# Resistor_Module.net
KiCad netlist of a schematic drawn in EAGLE
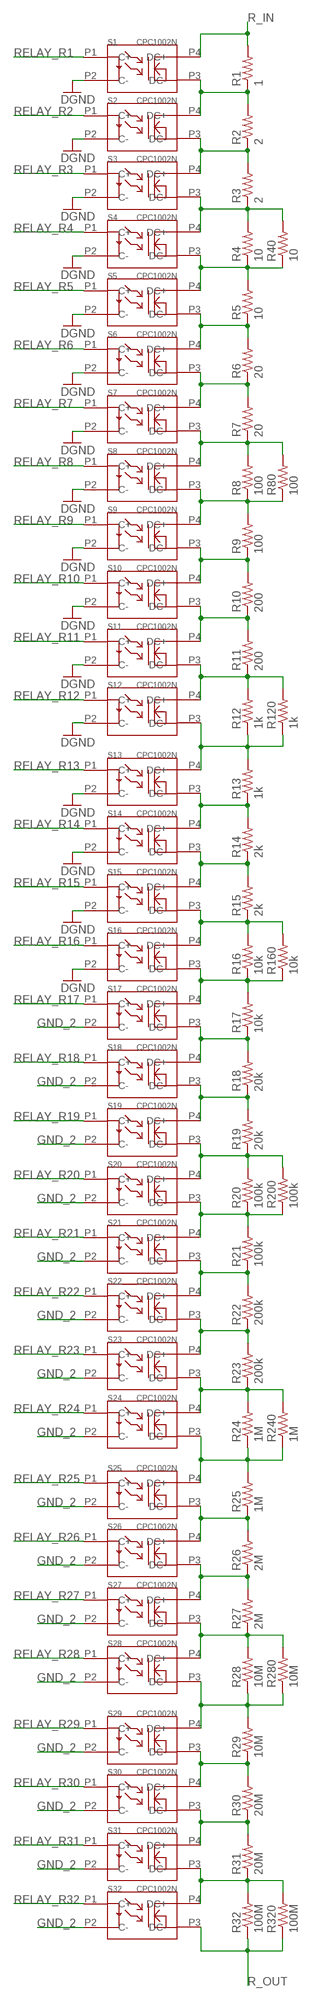
[diagram p0: schematic, sheet 1]
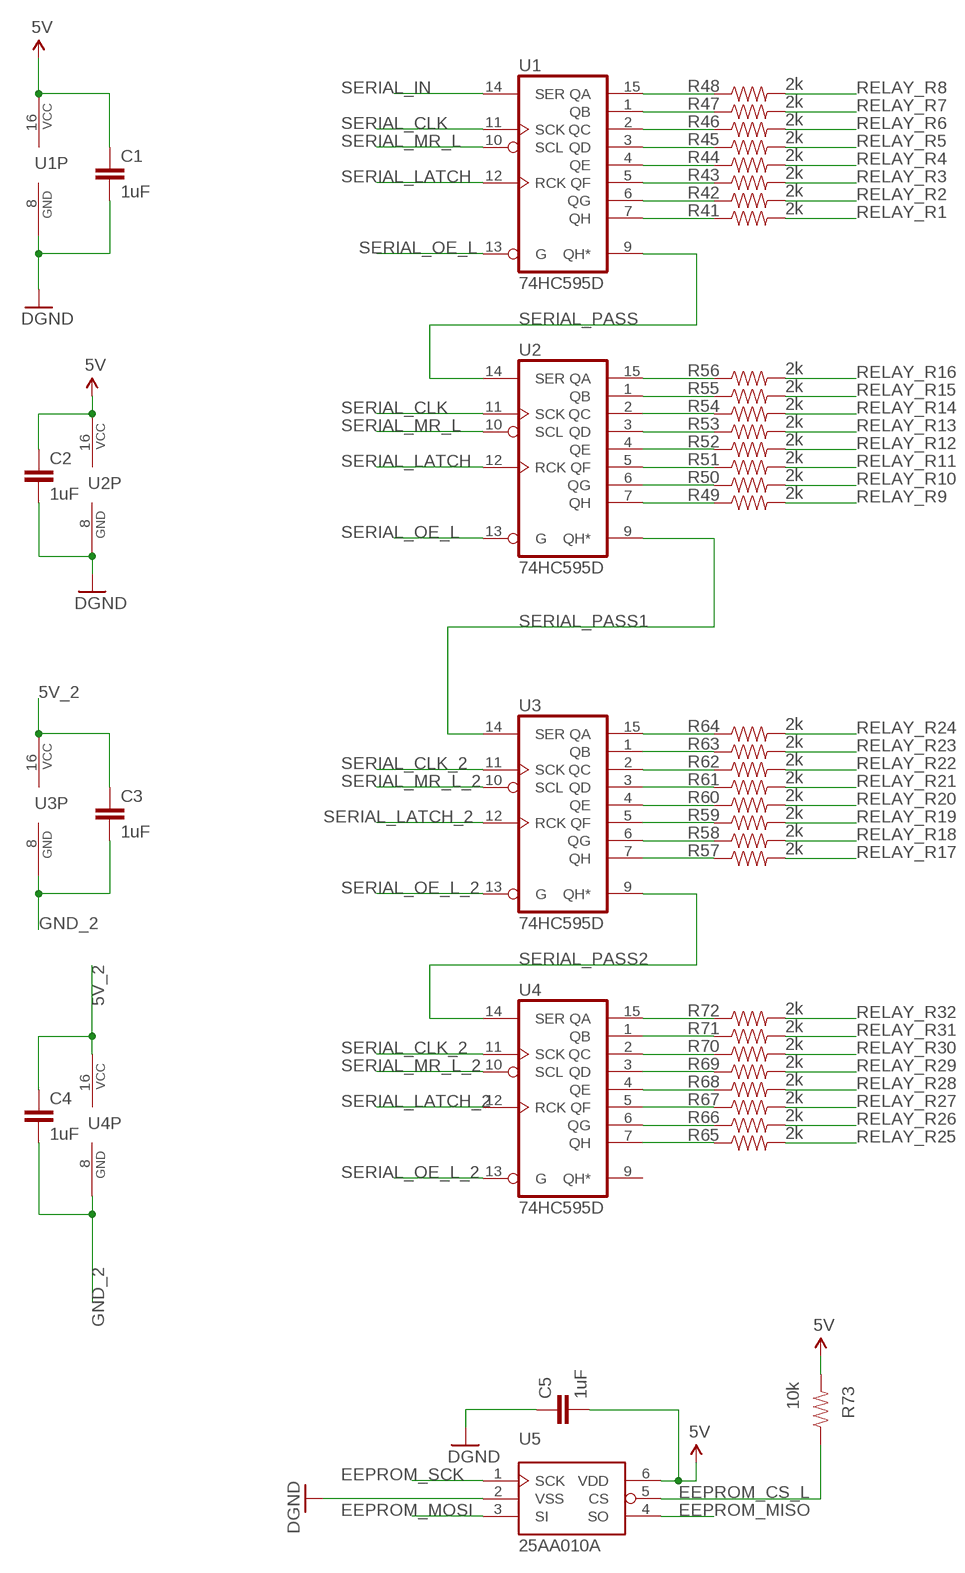
[diagram p1: schematic, sheet 2]
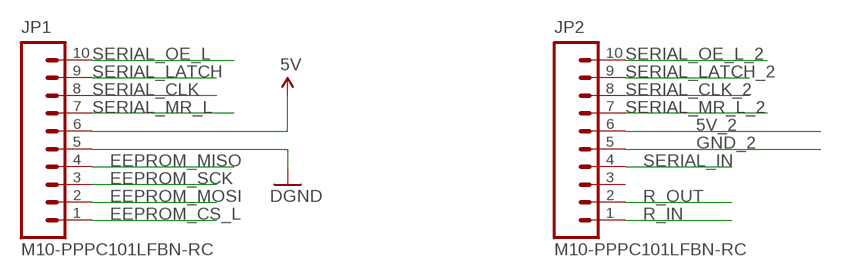
[diagram p2: schematic, sheet 3]
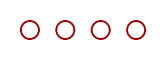
[diagram p3: schematic, sheet 4]

(export (version "E")
  (design (tool "Eeschema 10.0.6"))
  (components
    (comp (ref "STANDOFF1")
      (value "STAND-OFF")
      (footprint "eagle-import:STAND-OFF")
      (libsource (lib "eagle-import") (part "STAND-OFF"))
    )
    (comp (ref "STANDOFF2")
      (value "STAND-OFF")
      (footprint "eagle-import:STAND-OFF")
      (libsource (lib "eagle-import") (part "STAND-OFF"))
    )
    (comp (ref "STANDOFF3")
      (value "STAND-OFF")
      (footprint "eagle-import:STAND-OFF")
      (libsource (lib "eagle-import") (part "STAND-OFF"))
    )
    (comp (ref "STANDOFF4")
      (value "STAND-OFF")
      (footprint "eagle-import:STAND-OFF")
      (libsource (lib "eagle-import") (part "STAND-OFF"))
    )
    (comp (ref "JP1")
      (value "M10-PPPC101LFBN-RC")
      (footprint "eagle-import:PPPC101LFBN-RC")
      (libsource (lib "eagle-import") (part "M10-PPPC101LFBN-RC"))
    )
    (comp (ref "JP2")
      (value "M10-PPPC101LFBN-RC")
      (footprint "eagle-import:PPPC101LFBN-RC")
      (libsource (lib "eagle-import") (part "M10-PPPC101LFBN-RC"))
    )
    (comp (ref "C1")
      (value "1uF")
      (footprint "eagle-import:0603-CAP")
      (libsource (lib "eagle-import") (part "CAP0603-CAP"))
    )
    (comp (ref "C2")
      (value "1uF")
      (footprint "eagle-import:0603-CAP")
      (libsource (lib "eagle-import") (part "CAP0603-CAP"))
    )
    (comp (ref "C3")
      (value "1uF")
      (footprint "eagle-import:0603-CAP")
      (libsource (lib "eagle-import") (part "CAP0603-CAP"))
    )
    (comp (ref "C4")
      (value "1uF")
      (footprint "eagle-import:0603-CAP")
      (libsource (lib "eagle-import") (part "CAP0603-CAP"))
    )
    (comp (ref "C5")
      (value "1uF")
      (footprint "eagle-import:0603-CAP")
      (libsource (lib "eagle-import") (part "CAP0603-CAP"))
    )
    (comp (ref "R41")
      (value "2k")
      (footprint "eagle-import:0603-RES")
      (libsource (lib "eagle-import") (part "RESISTOR0603-RES"))
    )
    (comp (ref "R42")
      (value "2k")
      (footprint "eagle-import:0603-RES")
      (libsource (lib "eagle-import") (part "RESISTOR0603-RES"))
    )
    (comp (ref "R43")
      (value "2k")
      (footprint "eagle-import:0603-RES")
      (libsource (lib "eagle-import") (part "RESISTOR0603-RES"))
    )
    (comp (ref "R44")
      (value "2k")
      (footprint "eagle-import:0603-RES")
      (libsource (lib "eagle-import") (part "RESISTOR0603-RES"))
    )
    (comp (ref "R45")
      (value "2k")
      (footprint "eagle-import:0603-RES")
      (libsource (lib "eagle-import") (part "RESISTOR0603-RES"))
    )
    (comp (ref "R46")
      (value "2k")
      (footprint "eagle-import:0603-RES")
      (libsource (lib "eagle-import") (part "RESISTOR0603-RES"))
    )
    (comp (ref "R47")
      (value "2k")
      (footprint "eagle-import:0603-RES")
      (libsource (lib "eagle-import") (part "RESISTOR0603-RES"))
    )
    (comp (ref "R48")
      (value "2k")
      (footprint "eagle-import:0603-RES")
      (libsource (lib "eagle-import") (part "RESISTOR0603-RES"))
    )
    (comp (ref "R49")
      (value "2k")
      (footprint "eagle-import:0603-RES")
      (libsource (lib "eagle-import") (part "RESISTOR0603-RES"))
    )
    (comp (ref "R50")
      (value "2k")
      (footprint "eagle-import:0603-RES")
      (libsource (lib "eagle-import") (part "RESISTOR0603-RES"))
    )
    (comp (ref "R51")
      (value "2k")
      (footprint "eagle-import:0603-RES")
      (libsource (lib "eagle-import") (part "RESISTOR0603-RES"))
    )
    (comp (ref "R52")
      (value "2k")
      (footprint "eagle-import:0603-RES")
      (libsource (lib "eagle-import") (part "RESISTOR0603-RES"))
    )
    (comp (ref "R53")
      (value "2k")
      (footprint "eagle-import:0603-RES")
      (libsource (lib "eagle-import") (part "RESISTOR0603-RES"))
    )
    (comp (ref "R54")
      (value "2k")
      (footprint "eagle-import:0603-RES")
      (libsource (lib "eagle-import") (part "RESISTOR0603-RES"))
    )
    (comp (ref "R55")
      (value "2k")
      (footprint "eagle-import:0603-RES")
      (libsource (lib "eagle-import") (part "RESISTOR0603-RES"))
    )
    (comp (ref "R56")
      (value "2k")
      (footprint "eagle-import:0603-RES")
      (libsource (lib "eagle-import") (part "RESISTOR0603-RES"))
    )
    (comp (ref "R57")
      (value "2k")
      (footprint "eagle-import:0603-RES")
      (libsource (lib "eagle-import") (part "RESISTOR0603-RES"))
    )
    (comp (ref "R58")
      (value "2k")
      (footprint "eagle-import:0603-RES")
      (libsource (lib "eagle-import") (part "RESISTOR0603-RES"))
    )
    (comp (ref "R59")
      (value "2k")
      (footprint "eagle-import:0603-RES")
      (libsource (lib "eagle-import") (part "RESISTOR0603-RES"))
    )
    (comp (ref "R60")
      (value "2k")
      (footprint "eagle-import:0603-RES")
      (libsource (lib "eagle-import") (part "RESISTOR0603-RES"))
    )
    (comp (ref "R61")
      (value "2k")
      (footprint "eagle-import:0603-RES")
      (libsource (lib "eagle-import") (part "RESISTOR0603-RES"))
    )
    (comp (ref "R62")
      (value "2k")
      (footprint "eagle-import:0603-RES")
      (libsource (lib "eagle-import") (part "RESISTOR0603-RES"))
    )
    (comp (ref "R63")
      (value "2k")
      (footprint "eagle-import:0603-RES")
      (libsource (lib "eagle-import") (part "RESISTOR0603-RES"))
    )
    (comp (ref "R64")
      (value "2k")
      (footprint "eagle-import:0603-RES")
      (libsource (lib "eagle-import") (part "RESISTOR0603-RES"))
    )
    (comp (ref "R65")
      (value "2k")
      (footprint "eagle-import:0603-RES")
      (libsource (lib "eagle-import") (part "RESISTOR0603-RES"))
    )
    (comp (ref "R66")
      (value "2k")
      (footprint "eagle-import:0603-RES")
      (libsource (lib "eagle-import") (part "RESISTOR0603-RES"))
    )
    (comp (ref "R67")
      (value "2k")
      (footprint "eagle-import:0603-RES")
      (libsource (lib "eagle-import") (part "RESISTOR0603-RES"))
    )
    (comp (ref "R68")
      (value "2k")
      (footprint "eagle-import:0603-RES")
      (libsource (lib "eagle-import") (part "RESISTOR0603-RES"))
    )
    (comp (ref "R69")
      (value "2k")
      (footprint "eagle-import:0603-RES")
      (libsource (lib "eagle-import") (part "RESISTOR0603-RES"))
    )
    (comp (ref "R70")
      (value "2k")
      (footprint "eagle-import:0603-RES")
      (libsource (lib "eagle-import") (part "RESISTOR0603-RES"))
    )
    (comp (ref "R71")
      (value "2k")
      (footprint "eagle-import:0603-RES")
      (libsource (lib "eagle-import") (part "RESISTOR0603-RES"))
    )
    (comp (ref "R72")
      (value "2k")
      (footprint "eagle-import:0603-RES")
      (libsource (lib "eagle-import") (part "RESISTOR0603-RES"))
    )
    (comp (ref "R73")
      (value "10k")
      (footprint "eagle-import:0603-RES")
      (libsource (lib "eagle-import") (part "RESISTOR0603-RES"))
    )
    (comp (ref "U1")
      (value "74HC595D")
      (footprint "eagle-import:SO16")
      (libsource (lib "eagle-import") (part "74595DHC"))
    )
    (comp (ref "U2")
      (value "74HC595D")
      (footprint "eagle-import:SO16")
      (libsource (lib "eagle-import") (part "74595DHC"))
    )
    (comp (ref "U3")
      (value "74HC595D")
      (footprint "eagle-import:SO16")
      (libsource (lib "eagle-import") (part "74595DHC"))
    )
    (comp (ref "U4")
      (value "74HC595D")
      (footprint "eagle-import:SO16")
      (libsource (lib "eagle-import") (part "74595DHC"))
    )
    (comp (ref "U5")
      (value "25AA010A")
      (footprint "eagle-import:SOT23-6")
      (libsource (lib "eagle-import") (part "25AA010A"))
    )
    (comp (ref "R1")
      (value "1")
      (footprint "eagle-import:1206")
      (libsource (lib "eagle-import") (part "RESISTOR1206"))
    )
    (comp (ref "R2")
      (value "2")
      (footprint "eagle-import:1206")
      (libsource (lib "eagle-import") (part "RESISTOR1206"))
    )
    (comp (ref "R3")
      (value "2")
      (footprint "eagle-import:1206")
      (libsource (lib "eagle-import") (part "RESISTOR1206"))
    )
    (comp (ref "R4")
      (value "10")
      (footprint "eagle-import:1206")
      (libsource (lib "eagle-import") (part "RESISTOR1206"))
    )
    (comp (ref "R5")
      (value "10")
      (footprint "eagle-import:1206")
      (libsource (lib "eagle-import") (part "RESISTOR1206"))
    )
    (comp (ref "R6")
      (value "20")
      (footprint "eagle-import:1206")
      (libsource (lib "eagle-import") (part "RESISTOR1206"))
    )
    (comp (ref "R7")
      (value "20")
      (footprint "eagle-import:1206")
      (libsource (lib "eagle-import") (part "RESISTOR1206"))
    )
    (comp (ref "R8")
      (value "100")
      (footprint "eagle-import:1206")
      (libsource (lib "eagle-import") (part "RESISTOR1206"))
    )
    (comp (ref "R9")
      (value "100")
      (footprint "eagle-import:1206")
      (libsource (lib "eagle-import") (part "RESISTOR1206"))
    )
    (comp (ref "R10")
      (value "200")
      (footprint "eagle-import:1206")
      (libsource (lib "eagle-import") (part "RESISTOR1206"))
    )
    (comp (ref "R11")
      (value "200")
      (footprint "eagle-import:1206")
      (libsource (lib "eagle-import") (part "RESISTOR1206"))
    )
    (comp (ref "R12")
      (value "1k")
      (footprint "eagle-import:1206")
      (libsource (lib "eagle-import") (part "RESISTOR1206"))
    )
    (comp (ref "R13")
      (value "1k")
      (footprint "eagle-import:1206")
      (libsource (lib "eagle-import") (part "RESISTOR1206"))
    )
    (comp (ref "R14")
      (value "2k")
      (footprint "eagle-import:1206")
      (libsource (lib "eagle-import") (part "RESISTOR1206"))
    )
    (comp (ref "R15")
      (value "2k")
      (footprint "eagle-import:1206")
      (libsource (lib "eagle-import") (part "RESISTOR1206"))
    )
    (comp (ref "R16")
      (value "10k")
      (footprint "eagle-import:1206")
      (libsource (lib "eagle-import") (part "RESISTOR1206"))
    )
    (comp (ref "R17")
      (value "10k")
      (footprint "eagle-import:1206")
      (libsource (lib "eagle-import") (part "RESISTOR1206"))
    )
    (comp (ref "R18")
      (value "20k")
      (footprint "eagle-import:1206")
      (libsource (lib "eagle-import") (part "RESISTOR1206"))
    )
    (comp (ref "R19")
      (value "20k")
      (footprint "eagle-import:1206")
      (libsource (lib "eagle-import") (part "RESISTOR1206"))
    )
    (comp (ref "R20")
      (value "100k")
      (footprint "eagle-import:1206")
      (libsource (lib "eagle-import") (part "RESISTOR1206"))
    )
    (comp (ref "R21")
      (value "100k")
      (footprint "eagle-import:1206")
      (libsource (lib "eagle-import") (part "RESISTOR1206"))
    )
    (comp (ref "R22")
      (value "200k")
      (footprint "eagle-import:1206")
      (libsource (lib "eagle-import") (part "RESISTOR1206"))
    )
    (comp (ref "R23")
      (value "200k")
      (footprint "eagle-import:1206")
      (libsource (lib "eagle-import") (part "RESISTOR1206"))
    )
    (comp (ref "R24")
      (value "1M")
      (footprint "eagle-import:1206")
      (libsource (lib "eagle-import") (part "RESISTOR1206"))
    )
    (comp (ref "R25")
      (value "1M")
      (footprint "eagle-import:1206")
      (libsource (lib "eagle-import") (part "RESISTOR1206"))
    )
    (comp (ref "R26")
      (value "2M")
      (footprint "eagle-import:1206")
      (libsource (lib "eagle-import") (part "RESISTOR1206"))
    )
    (comp (ref "R27")
      (value "2M")
      (footprint "eagle-import:1206")
      (libsource (lib "eagle-import") (part "RESISTOR1206"))
    )
    (comp (ref "R28")
      (value "10M")
      (footprint "eagle-import:1206")
      (libsource (lib "eagle-import") (part "RESISTOR1206"))
    )
    (comp (ref "R29")
      (value "10M")
      (footprint "eagle-import:1206")
      (libsource (lib "eagle-import") (part "RESISTOR1206"))
    )
    (comp (ref "R30")
      (value "20M")
      (footprint "eagle-import:1206")
      (libsource (lib "eagle-import") (part "RESISTOR1206"))
    )
    (comp (ref "R31")
      (value "20M")
      (footprint "eagle-import:1206")
      (libsource (lib "eagle-import") (part "RESISTOR1206"))
    )
    (comp (ref "R32")
      (value "100M")
      (footprint "eagle-import:1206")
      (libsource (lib "eagle-import") (part "RESISTOR1206"))
    )
    (comp (ref "R40")
      (value "10")
      (footprint "eagle-import:1206")
      (libsource (lib "eagle-import") (part "RESISTOR1206"))
    )
    (comp (ref "R80")
      (value "100")
      (footprint "eagle-import:1206")
      (libsource (lib "eagle-import") (part "RESISTOR1206"))
    )
    (comp (ref "R120")
      (value "1k")
      (footprint "eagle-import:1206")
      (libsource (lib "eagle-import") (part "RESISTOR1206"))
    )
    (comp (ref "R160")
      (value "10k")
      (footprint "eagle-import:1206")
      (libsource (lib "eagle-import") (part "RESISTOR1206"))
    )
    (comp (ref "R200")
      (value "100k")
      (footprint "eagle-import:1206")
      (libsource (lib "eagle-import") (part "RESISTOR1206"))
    )
    (comp (ref "R240")
      (value "1M")
      (footprint "eagle-import:1206")
      (libsource (lib "eagle-import") (part "RESISTOR1206"))
    )
    (comp (ref "R280")
      (value "10M")
      (footprint "eagle-import:1206")
      (libsource (lib "eagle-import") (part "RESISTOR1206"))
    )
    (comp (ref "R320")
      (value "100M")
      (footprint "eagle-import:1206")
      (libsource (lib "eagle-import") (part "RESISTOR1206"))
    )
    (comp (ref "S1")
      (value "CPC1002N")
      (footprint "eagle-import:CPC1002N")
      (libsource (lib "eagle-import") (part "CPC1002N"))
    )
    (comp (ref "S2")
      (value "CPC1002N")
      (footprint "eagle-import:CPC1002N")
      (libsource (lib "eagle-import") (part "CPC1002N"))
    )
    (comp (ref "S3")
      (value "CPC1002N")
      (footprint "eagle-import:CPC1002N")
      (libsource (lib "eagle-import") (part "CPC1002N"))
    )
    (comp (ref "S4")
      (value "CPC1002N")
      (footprint "eagle-import:CPC1002N")
      (libsource (lib "eagle-import") (part "CPC1002N"))
    )
    (comp (ref "S5")
      (value "CPC1002N")
      (footprint "eagle-import:CPC1002N")
      (libsource (lib "eagle-import") (part "CPC1002N"))
    )
    (comp (ref "S6")
      (value "CPC1002N")
      (footprint "eagle-import:CPC1002N")
      (libsource (lib "eagle-import") (part "CPC1002N"))
    )
    (comp (ref "S7")
      (value "CPC1002N")
      (footprint "eagle-import:CPC1002N")
      (libsource (lib "eagle-import") (part "CPC1002N"))
    )
    (comp (ref "S8")
      (value "CPC1002N")
      (footprint "eagle-import:CPC1002N")
      (libsource (lib "eagle-import") (part "CPC1002N"))
    )
    (comp (ref "S9")
      (value "CPC1002N")
      (footprint "eagle-import:CPC1002N")
      (libsource (lib "eagle-import") (part "CPC1002N"))
    )
    (comp (ref "S10")
      (value "CPC1002N")
      (footprint "eagle-import:CPC1002N")
      (libsource (lib "eagle-import") (part "CPC1002N"))
    )
    (comp (ref "S11")
      (value "CPC1002N")
      (footprint "eagle-import:CPC1002N")
      (libsource (lib "eagle-import") (part "CPC1002N"))
    )
    (comp (ref "S12")
      (value "CPC1002N")
      (footprint "eagle-import:CPC1002N")
      (libsource (lib "eagle-import") (part "CPC1002N"))
    )
    (comp (ref "S13")
      (value "CPC1002N")
      (footprint "eagle-import:CPC1002N")
      (libsource (lib "eagle-import") (part "CPC1002N"))
    )
    (comp (ref "S14")
      (value "CPC1002N")
      (footprint "eagle-import:CPC1002N")
      (libsource (lib "eagle-import") (part "CPC1002N"))
    )
    (comp (ref "S15")
      (value "CPC1002N")
      (footprint "eagle-import:CPC1002N")
      (libsource (lib "eagle-import") (part "CPC1002N"))
    )
    (comp (ref "S16")
      (value "CPC1002N")
      (footprint "eagle-import:CPC1002N")
      (libsource (lib "eagle-import") (part "CPC1002N"))
    )
    (comp (ref "S17")
      (value "CPC1002N")
      (footprint "eagle-import:CPC1002N")
      (libsource (lib "eagle-import") (part "CPC1002N"))
    )
    (comp (ref "S18")
      (value "CPC1002N")
      (footprint "eagle-import:CPC1002N")
      (libsource (lib "eagle-import") (part "CPC1002N"))
    )
    (comp (ref "S19")
      (value "CPC1002N")
      (footprint "eagle-import:CPC1002N")
      (libsource (lib "eagle-import") (part "CPC1002N"))
    )
    (comp (ref "S20")
      (value "CPC1002N")
      (footprint "eagle-import:CPC1002N")
      (libsource (lib "eagle-import") (part "CPC1002N"))
    )
    (comp (ref "S21")
      (value "CPC1002N")
      (footprint "eagle-import:CPC1002N")
      (libsource (lib "eagle-import") (part "CPC1002N"))
    )
    (comp (ref "S22")
      (value "CPC1002N")
      (footprint "eagle-import:CPC1002N")
      (libsource (lib "eagle-import") (part "CPC1002N"))
    )
    (comp (ref "S23")
      (value "CPC1002N")
      (footprint "eagle-import:CPC1002N")
      (libsource (lib "eagle-import") (part "CPC1002N"))
    )
    (comp (ref "S24")
      (value "CPC1002N")
      (footprint "eagle-import:CPC1002N")
      (libsource (lib "eagle-import") (part "CPC1002N"))
    )
    (comp (ref "S25")
      (value "CPC1002N")
      (footprint "eagle-import:CPC1002N")
      (libsource (lib "eagle-import") (part "CPC1002N"))
    )
    (comp (ref "S26")
      (value "CPC1002N")
      (footprint "eagle-import:CPC1002N")
      (libsource (lib "eagle-import") (part "CPC1002N"))
    )
    (comp (ref "S27")
      (value "CPC1002N")
      (footprint "eagle-import:CPC1002N")
      (libsource (lib "eagle-import") (part "CPC1002N"))
    )
    (comp (ref "S28")
      (value "CPC1002N")
      (footprint "eagle-import:CPC1002N")
      (libsource (lib "eagle-import") (part "CPC1002N"))
    )
    (comp (ref "S29")
      (value "CPC1002N")
      (footprint "eagle-import:CPC1002N")
      (libsource (lib "eagle-import") (part "CPC1002N"))
    )
    (comp (ref "S30")
      (value "CPC1002N")
      (footprint "eagle-import:CPC1002N")
      (libsource (lib "eagle-import") (part "CPC1002N"))
    )
    (comp (ref "S31")
      (value "CPC1002N")
      (footprint "eagle-import:CPC1002N")
      (libsource (lib "eagle-import") (part "CPC1002N"))
    )
    (comp (ref "S32")
      (value "CPC1002N")
      (footprint "eagle-import:CPC1002N")
      (libsource (lib "eagle-import") (part "CPC1002N"))
    )
  )
  (nets
    (net (code "1") (name "5V") (class "Default")
      (node (ref "C1") (pin "1") (pinfunction "1_1") (pintype "passive"))
      (node (ref "C2") (pin "1") (pinfunction "1_1") (pintype "passive"))
      (node (ref "C5") (pin "2") (pinfunction "2_2") (pintype "passive"))
      (node (ref "JP1") (pin "6") (pinfunction "6_6") (pintype "passive"))
      (node (ref "R73") (pin "2") (pinfunction "2_2") (pintype "passive"))
      (node (ref "U1") (pin "16") (pinfunction "VCC_16") (pintype "power_in"))
      (node (ref "U2") (pin "16") (pinfunction "VCC_16") (pintype "power_in"))
      (node (ref "U5") (pin "6") (pinfunction "VDD_6") (pintype "power_in"))
    )
    (net (code "2") (name "5V_2") (class "Default")
      (node (ref "C3") (pin "1") (pinfunction "1_1") (pintype "passive"))
      (node (ref "C4") (pin "1") (pinfunction "1_1") (pintype "passive"))
      (node (ref "JP2") (pin "6") (pinfunction "6_6") (pintype "passive"))
      (node (ref "U3") (pin "16") (pinfunction "VCC_16") (pintype "power_in"))
      (node (ref "U4") (pin "16") (pinfunction "VCC_16") (pintype "power_in"))
    )
    (net (code "3") (name "EEPROM_CS_L") (class "Default")
      (node (ref "JP1") (pin "1") (pinfunction "1_1") (pintype "passive"))
      (node (ref "R73") (pin "1") (pinfunction "1_1") (pintype "passive"))
      (node (ref "U5") (pin "5") (pinfunction "CS_5") (pintype "bidirectional"))
    )
    (net (code "4") (name "EEPROM_MISO") (class "Default")
      (node (ref "JP1") (pin "4") (pinfunction "4_4") (pintype "passive"))
      (node (ref "U5") (pin "4") (pinfunction "SO_4") (pintype "output"))
    )
    (net (code "5") (name "EEPROM_MOSI") (class "Default")
      (node (ref "JP1") (pin "2") (pinfunction "2_2") (pintype "passive"))
      (node (ref "U5") (pin "3") (pinfunction "SI_3") (pintype "input"))
    )
    (net (code "6") (name "EEPROM_SCK") (class "Default")
      (node (ref "JP1") (pin "3") (pinfunction "3_3") (pintype "passive"))
      (node (ref "U5") (pin "1") (pinfunction "SCK_1") (pintype "input"))
    )
    (net (code "7") (name "GND") (class "Default")
      (node (ref "C1") (pin "2") (pinfunction "2_2") (pintype "passive"))
      (node (ref "C2") (pin "2") (pinfunction "2_2") (pintype "passive"))
      (node (ref "C5") (pin "1") (pinfunction "1_1") (pintype "passive"))
      (node (ref "JP1") (pin "5") (pinfunction "5_5") (pintype "passive"))
      (node (ref "S1") (pin "P2") (pinfunction "C-_P2") (pintype "bidirectional"))
      (node (ref "S10") (pin "P2") (pinfunction "C-_P2") (pintype "bidirectional"))
      (node (ref "S11") (pin "P2") (pinfunction "C-_P2") (pintype "bidirectional"))
      (node (ref "S12") (pin "P2") (pinfunction "C-_P2") (pintype "bidirectional"))
      (node (ref "S13") (pin "P2") (pinfunction "C-_P2") (pintype "bidirectional"))
      (node (ref "S14") (pin "P2") (pinfunction "C-_P2") (pintype "bidirectional"))
      (node (ref "S15") (pin "P2") (pinfunction "C-_P2") (pintype "bidirectional"))
      (node (ref "S16") (pin "P2") (pinfunction "C-_P2") (pintype "bidirectional"))
      (node (ref "S2") (pin "P2") (pinfunction "C-_P2") (pintype "bidirectional"))
      (node (ref "S3") (pin "P2") (pinfunction "C-_P2") (pintype "bidirectional"))
      (node (ref "S4") (pin "P2") (pinfunction "C-_P2") (pintype "bidirectional"))
      (node (ref "S5") (pin "P2") (pinfunction "C-_P2") (pintype "bidirectional"))
      (node (ref "S6") (pin "P2") (pinfunction "C-_P2") (pintype "bidirectional"))
      (node (ref "S7") (pin "P2") (pinfunction "C-_P2") (pintype "bidirectional"))
      (node (ref "S8") (pin "P2") (pinfunction "C-_P2") (pintype "bidirectional"))
      (node (ref "S9") (pin "P2") (pinfunction "C-_P2") (pintype "bidirectional"))
      (node (ref "U1") (pin "8") (pinfunction "GND_8") (pintype "power_in"))
      (node (ref "U2") (pin "8") (pinfunction "GND_8") (pintype "power_in"))
      (node (ref "U5") (pin "2") (pinfunction "VSS_2") (pintype "power_in"))
    )
    (net (code "8") (name "GND_2") (class "Default")
      (node (ref "C3") (pin "2") (pinfunction "2_2") (pintype "passive"))
      (node (ref "C4") (pin "2") (pinfunction "2_2") (pintype "passive"))
      (node (ref "JP2") (pin "5") (pinfunction "5_5") (pintype "passive"))
      (node (ref "S17") (pin "P2") (pinfunction "C-_P2") (pintype "bidirectional"))
      (node (ref "S18") (pin "P2") (pinfunction "C-_P2") (pintype "bidirectional"))
      (node (ref "S19") (pin "P2") (pinfunction "C-_P2") (pintype "bidirectional"))
      (node (ref "S20") (pin "P2") (pinfunction "C-_P2") (pintype "bidirectional"))
      (node (ref "S21") (pin "P2") (pinfunction "C-_P2") (pintype "bidirectional"))
      (node (ref "S22") (pin "P2") (pinfunction "C-_P2") (pintype "bidirectional"))
      (node (ref "S23") (pin "P2") (pinfunction "C-_P2") (pintype "bidirectional"))
      (node (ref "S24") (pin "P2") (pinfunction "C-_P2") (pintype "bidirectional"))
      (node (ref "S25") (pin "P2") (pinfunction "C-_P2") (pintype "bidirectional"))
      (node (ref "S26") (pin "P2") (pinfunction "C-_P2") (pintype "bidirectional"))
      (node (ref "S27") (pin "P2") (pinfunction "C-_P2") (pintype "bidirectional"))
      (node (ref "S28") (pin "P2") (pinfunction "C-_P2") (pintype "bidirectional"))
      (node (ref "S29") (pin "P2") (pinfunction "C-_P2") (pintype "bidirectional"))
      (node (ref "S30") (pin "P2") (pinfunction "C-_P2") (pintype "bidirectional"))
      (node (ref "S31") (pin "P2") (pinfunction "C-_P2") (pintype "bidirectional"))
      (node (ref "S32") (pin "P2") (pinfunction "C-_P2") (pintype "bidirectional"))
      (node (ref "U3") (pin "8") (pinfunction "GND_8") (pintype "power_in"))
      (node (ref "U4") (pin "8") (pinfunction "GND_8") (pintype "power_in"))
    )
    (net (code "9") (name "Net-(S1-DC-)") (class "Default")
      (node (ref "R1") (pin "1") (pinfunction "1_1") (pintype "passive"))
      (node (ref "R2") (pin "2") (pinfunction "2_2") (pintype "passive"))
      (node (ref "S1") (pin "P3") (pinfunction "DC-_P3") (pintype "bidirectional"))
      (node (ref "S2") (pin "P4") (pinfunction "DC+_P4") (pintype "bidirectional"))
    )
    (net (code "10") (name "Net-(S2-DC-)") (class "Default")
      (node (ref "R2") (pin "1") (pinfunction "1_1") (pintype "passive"))
      (node (ref "R3") (pin "2") (pinfunction "2_2") (pintype "passive"))
      (node (ref "S2") (pin "P3") (pinfunction "DC-_P3") (pintype "bidirectional"))
      (node (ref "S3") (pin "P4") (pinfunction "DC+_P4") (pintype "bidirectional"))
    )
    (net (code "11") (name "Net-(S3-DC-)") (class "Default")
      (node (ref "R3") (pin "1") (pinfunction "1_1") (pintype "passive"))
      (node (ref "R4") (pin "2") (pinfunction "2_2") (pintype "passive"))
      (node (ref "R40") (pin "2") (pinfunction "2_2") (pintype "passive"))
      (node (ref "S3") (pin "P3") (pinfunction "DC-_P3") (pintype "bidirectional"))
      (node (ref "S4") (pin "P4") (pinfunction "DC+_P4") (pintype "bidirectional"))
    )
    (net (code "12") (name "Net-(S4-DC-)") (class "Default")
      (node (ref "R4") (pin "1") (pinfunction "1_1") (pintype "passive"))
      (node (ref "R40") (pin "1") (pinfunction "1_1") (pintype "passive"))
      (node (ref "R5") (pin "2") (pinfunction "2_2") (pintype "passive"))
      (node (ref "S4") (pin "P3") (pinfunction "DC-_P3") (pintype "bidirectional"))
      (node (ref "S5") (pin "P4") (pinfunction "DC+_P4") (pintype "bidirectional"))
    )
    (net (code "13") (name "Net-(S5-DC-)") (class "Default")
      (node (ref "R5") (pin "1") (pinfunction "1_1") (pintype "passive"))
      (node (ref "R6") (pin "2") (pinfunction "2_2") (pintype "passive"))
      (node (ref "S5") (pin "P3") (pinfunction "DC-_P3") (pintype "bidirectional"))
      (node (ref "S6") (pin "P4") (pinfunction "DC+_P4") (pintype "bidirectional"))
    )
    (net (code "14") (name "Net-(S6-DC-)") (class "Default")
      (node (ref "R6") (pin "1") (pinfunction "1_1") (pintype "passive"))
      (node (ref "R7") (pin "2") (pinfunction "2_2") (pintype "passive"))
      (node (ref "S6") (pin "P3") (pinfunction "DC-_P3") (pintype "bidirectional"))
      (node (ref "S7") (pin "P4") (pinfunction "DC+_P4") (pintype "bidirectional"))
    )
    (net (code "15") (name "Net-(S7-DC-)") (class "Default")
      (node (ref "R7") (pin "1") (pinfunction "1_1") (pintype "passive"))
      (node (ref "R8") (pin "2") (pinfunction "2_2") (pintype "passive"))
      (node (ref "R80") (pin "2") (pinfunction "2_2") (pintype "passive"))
      (node (ref "S7") (pin "P3") (pinfunction "DC-_P3") (pintype "bidirectional"))
      (node (ref "S8") (pin "P4") (pinfunction "DC+_P4") (pintype "bidirectional"))
    )
    (net (code "16") (name "Net-(S8-DC-)") (class "Default")
      (node (ref "R8") (pin "1") (pinfunction "1_1") (pintype "passive"))
      (node (ref "R80") (pin "1") (pinfunction "1_1") (pintype "passive"))
      (node (ref "R9") (pin "2") (pinfunction "2_2") (pintype "passive"))
      (node (ref "S8") (pin "P3") (pinfunction "DC-_P3") (pintype "bidirectional"))
      (node (ref "S9") (pin "P4") (pinfunction "DC+_P4") (pintype "bidirectional"))
    )
    (net (code "17") (name "Net-(S10-DC+)") (class "Default")
      (node (ref "R10") (pin "2") (pinfunction "2_2") (pintype "passive"))
      (node (ref "R9") (pin "1") (pinfunction "1_1") (pintype "passive"))
      (node (ref "S10") (pin "P4") (pinfunction "DC+_P4") (pintype "bidirectional"))
      (node (ref "S9") (pin "P3") (pinfunction "DC-_P3") (pintype "bidirectional"))
    )
    (net (code "18") (name "Net-(S10-DC-)") (class "Default")
      (node (ref "R10") (pin "1") (pinfunction "1_1") (pintype "passive"))
      (node (ref "R11") (pin "2") (pinfunction "2_2") (pintype "passive"))
      (node (ref "S10") (pin "P3") (pinfunction "DC-_P3") (pintype "bidirectional"))
      (node (ref "S11") (pin "P4") (pinfunction "DC+_P4") (pintype "bidirectional"))
    )
    (net (code "19") (name "Net-(S11-DC-)") (class "Default")
      (node (ref "R11") (pin "1") (pinfunction "1_1") (pintype "passive"))
      (node (ref "R12") (pin "2") (pinfunction "2_2") (pintype "passive"))
      (node (ref "R120") (pin "2") (pinfunction "2_2") (pintype "passive"))
      (node (ref "S11") (pin "P3") (pinfunction "DC-_P3") (pintype "bidirectional"))
      (node (ref "S12") (pin "P4") (pinfunction "DC+_P4") (pintype "bidirectional"))
    )
    (net (code "20") (name "Net-(S12-DC-)") (class "Default")
      (node (ref "R12") (pin "1") (pinfunction "1_1") (pintype "passive"))
      (node (ref "R120") (pin "1") (pinfunction "1_1") (pintype "passive"))
      (node (ref "R13") (pin "2") (pinfunction "2_2") (pintype "passive"))
      (node (ref "S12") (pin "P3") (pinfunction "DC-_P3") (pintype "bidirectional"))
      (node (ref "S13") (pin "P4") (pinfunction "DC+_P4") (pintype "bidirectional"))
    )
    (net (code "21") (name "Net-(S13-DC-)") (class "Default")
      (node (ref "R13") (pin "1") (pinfunction "1_1") (pintype "passive"))
      (node (ref "R14") (pin "2") (pinfunction "2_2") (pintype "passive"))
      (node (ref "S13") (pin "P3") (pinfunction "DC-_P3") (pintype "bidirectional"))
      (node (ref "S14") (pin "P4") (pinfunction "DC+_P4") (pintype "bidirectional"))
    )
    (net (code "22") (name "Net-(S14-DC-)") (class "Default")
      (node (ref "R14") (pin "1") (pinfunction "1_1") (pintype "passive"))
      (node (ref "R15") (pin "2") (pinfunction "2_2") (pintype "passive"))
      (node (ref "S14") (pin "P3") (pinfunction "DC-_P3") (pintype "bidirectional"))
      (node (ref "S15") (pin "P4") (pinfunction "DC+_P4") (pintype "bidirectional"))
    )
    (net (code "23") (name "Net-(S15-DC-)") (class "Default")
      (node (ref "R15") (pin "1") (pinfunction "1_1") (pintype "passive"))
      (node (ref "R16") (pin "2") (pinfunction "2_2") (pintype "passive"))
      (node (ref "R160") (pin "2") (pinfunction "2_2") (pintype "passive"))
      (node (ref "S15") (pin "P3") (pinfunction "DC-_P3") (pintype "bidirectional"))
      (node (ref "S16") (pin "P4") (pinfunction "DC+_P4") (pintype "bidirectional"))
    )
    (net (code "24") (name "Net-(S16-DC-)") (class "Default")
      (node (ref "R16") (pin "1") (pinfunction "1_1") (pintype "passive"))
      (node (ref "R160") (pin "1") (pinfunction "1_1") (pintype "passive"))
      (node (ref "R17") (pin "2") (pinfunction "2_2") (pintype "passive"))
      (node (ref "S16") (pin "P3") (pinfunction "DC-_P3") (pintype "bidirectional"))
      (node (ref "S17") (pin "P4") (pinfunction "DC+_P4") (pintype "bidirectional"))
    )
    (net (code "25") (name "Net-(S17-DC-)") (class "Default")
      (node (ref "R17") (pin "1") (pinfunction "1_1") (pintype "passive"))
      (node (ref "R18") (pin "2") (pinfunction "2_2") (pintype "passive"))
      (node (ref "S17") (pin "P3") (pinfunction "DC-_P3") (pintype "bidirectional"))
      (node (ref "S18") (pin "P4") (pinfunction "DC+_P4") (pintype "bidirectional"))
    )
    (net (code "26") (name "Net-(S18-DC-)") (class "Default")
      (node (ref "R18") (pin "1") (pinfunction "1_1") (pintype "passive"))
      (node (ref "R19") (pin "2") (pinfunction "2_2") (pintype "passive"))
      (node (ref "S18") (pin "P3") (pinfunction "DC-_P3") (pintype "bidirectional"))
      (node (ref "S19") (pin "P4") (pinfunction "DC+_P4") (pintype "bidirectional"))
    )
    (net (code "27") (name "Net-(S19-DC-)") (class "Default")
      (node (ref "R19") (pin "1") (pinfunction "1_1") (pintype "passive"))
      (node (ref "R20") (pin "2") (pinfunction "2_2") (pintype "passive"))
      (node (ref "R200") (pin "2") (pinfunction "2_2") (pintype "passive"))
      (node (ref "S19") (pin "P3") (pinfunction "DC-_P3") (pintype "bidirectional"))
      (node (ref "S20") (pin "P4") (pinfunction "DC+_P4") (pintype "bidirectional"))
    )
    (net (code "28") (name "Net-(S20-DC-)") (class "Default")
      (node (ref "R20") (pin "1") (pinfunction "1_1") (pintype "passive"))
      (node (ref "R200") (pin "1") (pinfunction "1_1") (pintype "passive"))
      (node (ref "R21") (pin "2") (pinfunction "2_2") (pintype "passive"))
      (node (ref "S20") (pin "P3") (pinfunction "DC-_P3") (pintype "bidirectional"))
      (node (ref "S21") (pin "P4") (pinfunction "DC+_P4") (pintype "bidirectional"))
    )
    (net (code "29") (name "Net-(S21-DC-)") (class "Default")
      (node (ref "R21") (pin "1") (pinfunction "1_1") (pintype "passive"))
      (node (ref "R22") (pin "2") (pinfunction "2_2") (pintype "passive"))
      (node (ref "S21") (pin "P3") (pinfunction "DC-_P3") (pintype "bidirectional"))
      (node (ref "S22") (pin "P4") (pinfunction "DC+_P4") (pintype "bidirectional"))
    )
    (net (code "30") (name "Net-(S22-DC-)") (class "Default")
      (node (ref "R22") (pin "1") (pinfunction "1_1") (pintype "passive"))
      (node (ref "R23") (pin "2") (pinfunction "2_2") (pintype "passive"))
      (node (ref "S22") (pin "P3") (pinfunction "DC-_P3") (pintype "bidirectional"))
      (node (ref "S23") (pin "P4") (pinfunction "DC+_P4") (pintype "bidirectional"))
    )
    (net (code "31") (name "Net-(S23-DC-)") (class "Default")
      (node (ref "R23") (pin "1") (pinfunction "1_1") (pintype "passive"))
      (node (ref "R24") (pin "2") (pinfunction "2_2") (pintype "passive"))
      (node (ref "R240") (pin "2") (pinfunction "2_2") (pintype "passive"))
      (node (ref "S23") (pin "P3") (pinfunction "DC-_P3") (pintype "bidirectional"))
      (node (ref "S24") (pin "P4") (pinfunction "DC+_P4") (pintype "bidirectional"))
    )
    (net (code "32") (name "Net-(S24-DC-)") (class "Default")
      (node (ref "R24") (pin "1") (pinfunction "1_1") (pintype "passive"))
      (node (ref "R240") (pin "1") (pinfunction "1_1") (pintype "passive"))
      (node (ref "R25") (pin "2") (pinfunction "2_2") (pintype "passive"))
      (node (ref "S24") (pin "P3") (pinfunction "DC-_P3") (pintype "bidirectional"))
      (node (ref "S25") (pin "P4") (pinfunction "DC+_P4") (pintype "bidirectional"))
    )
    (net (code "33") (name "Net-(S25-DC-)") (class "Default")
      (node (ref "R25") (pin "1") (pinfunction "1_1") (pintype "passive"))
      (node (ref "R26") (pin "2") (pinfunction "2_2") (pintype "passive"))
      (node (ref "S25") (pin "P3") (pinfunction "DC-_P3") (pintype "bidirectional"))
      (node (ref "S26") (pin "P4") (pinfunction "DC+_P4") (pintype "bidirectional"))
    )
    (net (code "34") (name "Net-(S26-DC-)") (class "Default")
      (node (ref "R26") (pin "1") (pinfunction "1_1") (pintype "passive"))
      (node (ref "R27") (pin "2") (pinfunction "2_2") (pintype "passive"))
      (node (ref "S26") (pin "P3") (pinfunction "DC-_P3") (pintype "bidirectional"))
      (node (ref "S27") (pin "P4") (pinfunction "DC+_P4") (pintype "bidirectional"))
    )
    (net (code "35") (name "Net-(S27-DC-)") (class "Default")
      (node (ref "R27") (pin "1") (pinfunction "1_1") (pintype "passive"))
      (node (ref "R28") (pin "2") (pinfunction "2_2") (pintype "passive"))
      (node (ref "R280") (pin "2") (pinfunction "2_2") (pintype "passive"))
      (node (ref "S27") (pin "P3") (pinfunction "DC-_P3") (pintype "bidirectional"))
      (node (ref "S28") (pin "P4") (pinfunction "DC+_P4") (pintype "bidirectional"))
    )
    (net (code "36") (name "Net-(S28-DC-)") (class "Default")
      (node (ref "R28") (pin "1") (pinfunction "1_1") (pintype "passive"))
      (node (ref "R280") (pin "1") (pinfunction "1_1") (pintype "passive"))
      (node (ref "R29") (pin "2") (pinfunction "2_2") (pintype "passive"))
      (node (ref "S28") (pin "P3") (pinfunction "DC-_P3") (pintype "bidirectional"))
      (node (ref "S29") (pin "P4") (pinfunction "DC+_P4") (pintype "bidirectional"))
    )
    (net (code "37") (name "Net-(S29-DC-)") (class "Default")
      (node (ref "R29") (pin "1") (pinfunction "1_1") (pintype "passive"))
      (node (ref "R30") (pin "2") (pinfunction "2_2") (pintype "passive"))
      (node (ref "S29") (pin "P3") (pinfunction "DC-_P3") (pintype "bidirectional"))
      (node (ref "S30") (pin "P4") (pinfunction "DC+_P4") (pintype "bidirectional"))
    )
    (net (code "38") (name "Net-(S30-DC-)") (class "Default")
      (node (ref "R30") (pin "1") (pinfunction "1_1") (pintype "passive"))
      (node (ref "R31") (pin "2") (pinfunction "2_2") (pintype "passive"))
      (node (ref "S30") (pin "P3") (pinfunction "DC-_P3") (pintype "bidirectional"))
      (node (ref "S31") (pin "P4") (pinfunction "DC+_P4") (pintype "bidirectional"))
    )
    (net (code "39") (name "Net-(S31-DC-)") (class "Default")
      (node (ref "R31") (pin "1") (pinfunction "1_1") (pintype "passive"))
      (node (ref "R32") (pin "2") (pinfunction "2_2") (pintype "passive"))
      (node (ref "R320") (pin "2") (pinfunction "2_2") (pintype "passive"))
      (node (ref "S31") (pin "P3") (pinfunction "DC-_P3") (pintype "bidirectional"))
      (node (ref "S32") (pin "P4") (pinfunction "DC+_P4") (pintype "bidirectional"))
    )
    (net (code "40") (name "Net-(U1A-QA)") (class "Default")
      (node (ref "R48") (pin "1") (pinfunction "1_1") (pintype "passive"))
      (node (ref "U1") (pin "15") (pinfunction "QA_15") (pintype "tri_state"))
    )
    (net (code "41") (name "Net-(U1A-QB)") (class "Default")
      (node (ref "R47") (pin "1") (pinfunction "1_1") (pintype "passive"))
      (node (ref "U1") (pin "1") (pinfunction "QB_1") (pintype "tri_state"))
    )
    (net (code "42") (name "Net-(U1A-QC)") (class "Default")
      (node (ref "R46") (pin "1") (pinfunction "1_1") (pintype "passive"))
      (node (ref "U1") (pin "2") (pinfunction "QC_2") (pintype "tri_state"))
    )
    (net (code "43") (name "Net-(U1A-QD)") (class "Default")
      (node (ref "R45") (pin "1") (pinfunction "1_1") (pintype "passive"))
      (node (ref "U1") (pin "3") (pinfunction "QD_3") (pintype "tri_state"))
    )
    (net (code "44") (name "Net-(U1A-QE)") (class "Default")
      (node (ref "R44") (pin "1") (pinfunction "1_1") (pintype "passive"))
      (node (ref "U1") (pin "4") (pinfunction "QE_4") (pintype "tri_state"))
    )
    (net (code "45") (name "Net-(U1A-QF)") (class "Default")
      (node (ref "R43") (pin "1") (pinfunction "1_1") (pintype "passive"))
      (node (ref "U1") (pin "5") (pinfunction "QF_5") (pintype "tri_state"))
    )
    (net (code "46") (name "Net-(U1A-QG)") (class "Default")
      (node (ref "R42") (pin "1") (pinfunction "1_1") (pintype "passive"))
      (node (ref "U1") (pin "6") (pinfunction "QG_6") (pintype "tri_state"))
    )
    (net (code "47") (name "Net-(U1A-QH)") (class "Default")
      (node (ref "R41") (pin "1") (pinfunction "1_1") (pintype "passive"))
      (node (ref "U1") (pin "7") (pinfunction "QH_7") (pintype "tri_state"))
    )
    (net (code "48") (name "Net-(U2A-QA)") (class "Default")
      (node (ref "R56") (pin "1") (pinfunction "1_1") (pintype "passive"))
      (node (ref "U2") (pin "15") (pinfunction "QA_15") (pintype "tri_state"))
    )
    (net (code "49") (name "Net-(U2A-QB)") (class "Default")
      (node (ref "R55") (pin "1") (pinfunction "1_1") (pintype "passive"))
      (node (ref "U2") (pin "1") (pinfunction "QB_1") (pintype "tri_state"))
    )
    (net (code "50") (name "Net-(U2A-QC)") (class "Default")
      (node (ref "R54") (pin "1") (pinfunction "1_1") (pintype "passive"))
      (node (ref "U2") (pin "2") (pinfunction "QC_2") (pintype "tri_state"))
    )
    (net (code "51") (name "Net-(U2A-QD)") (class "Default")
      (node (ref "R53") (pin "1") (pinfunction "1_1") (pintype "passive"))
      (node (ref "U2") (pin "3") (pinfunction "QD_3") (pintype "tri_state"))
    )
    (net (code "52") (name "Net-(U2A-QE)") (class "Default")
      (node (ref "R52") (pin "1") (pinfunction "1_1") (pintype "passive"))
      (node (ref "U2") (pin "4") (pinfunction "QE_4") (pintype "tri_state"))
    )
    (net (code "53") (name "Net-(U2A-QF)") (class "Default")
      (node (ref "R51") (pin "1") (pinfunction "1_1") (pintype "passive"))
      (node (ref "U2") (pin "5") (pinfunction "QF_5") (pintype "tri_state"))
    )
    (net (code "54") (name "Net-(U2A-QG)") (class "Default")
      (node (ref "R50") (pin "1") (pinfunction "1_1") (pintype "passive"))
      (node (ref "U2") (pin "6") (pinfunction "QG_6") (pintype "tri_state"))
    )
    (net (code "55") (name "Net-(U2A-QH)") (class "Default")
      (node (ref "R49") (pin "1") (pinfunction "1_1") (pintype "passive"))
      (node (ref "U2") (pin "7") (pinfunction "QH_7") (pintype "tri_state"))
    )
    (net (code "56") (name "Net-(U3A-QA)") (class "Default")
      (node (ref "R64") (pin "1") (pinfunction "1_1") (pintype "passive"))
      (node (ref "U3") (pin "15") (pinfunction "QA_15") (pintype "tri_state"))
    )
    (net (code "57") (name "Net-(U3A-QB)") (class "Default")
      (node (ref "R63") (pin "1") (pinfunction "1_1") (pintype "passive"))
      (node (ref "U3") (pin "1") (pinfunction "QB_1") (pintype "tri_state"))
    )
    (net (code "58") (name "Net-(U3A-QC)") (class "Default")
      (node (ref "R62") (pin "1") (pinfunction "1_1") (pintype "passive"))
      (node (ref "U3") (pin "2") (pinfunction "QC_2") (pintype "tri_state"))
    )
    (net (code "59") (name "Net-(U3A-QD)") (class "Default")
      (node (ref "R61") (pin "1") (pinfunction "1_1") (pintype "passive"))
      (node (ref "U3") (pin "3") (pinfunction "QD_3") (pintype "tri_state"))
    )
    (net (code "60") (name "Net-(U3A-QE)") (class "Default")
      (node (ref "R60") (pin "1") (pinfunction "1_1") (pintype "passive"))
      (node (ref "U3") (pin "4") (pinfunction "QE_4") (pintype "tri_state"))
    )
    (net (code "61") (name "Net-(U3A-QF)") (class "Default")
      (node (ref "R59") (pin "1") (pinfunction "1_1") (pintype "passive"))
      (node (ref "U3") (pin "5") (pinfunction "QF_5") (pintype "tri_state"))
    )
    (net (code "62") (name "Net-(U3A-QG)") (class "Default")
      (node (ref "R58") (pin "1") (pinfunction "1_1") (pintype "passive"))
      (node (ref "U3") (pin "6") (pinfunction "QG_6") (pintype "tri_state"))
    )
    (net (code "63") (name "Net-(U3A-QH)") (class "Default")
      (node (ref "R57") (pin "1") (pinfunction "1_1") (pintype "passive"))
      (node (ref "U3") (pin "7") (pinfunction "QH_7") (pintype "tri_state"))
    )
    (net (code "64") (name "Net-(U4A-QA)") (class "Default")
      (node (ref "R72") (pin "1") (pinfunction "1_1") (pintype "passive"))
      (node (ref "U4") (pin "15") (pinfunction "QA_15") (pintype "tri_state"))
    )
    (net (code "65") (name "Net-(U4A-QB)") (class "Default")
      (node (ref "R71") (pin "1") (pinfunction "1_1") (pintype "passive"))
      (node (ref "U4") (pin "1") (pinfunction "QB_1") (pintype "tri_state"))
    )
    (net (code "66") (name "Net-(U4A-QC)") (class "Default")
      (node (ref "R70") (pin "1") (pinfunction "1_1") (pintype "passive"))
      (node (ref "U4") (pin "2") (pinfunction "QC_2") (pintype "tri_state"))
    )
    (net (code "67") (name "Net-(U4A-QD)") (class "Default")
      (node (ref "R69") (pin "1") (pinfunction "1_1") (pintype "passive"))
      (node (ref "U4") (pin "3") (pinfunction "QD_3") (pintype "tri_state"))
    )
    (net (code "68") (name "Net-(U4A-QE)") (class "Default")
      (node (ref "R68") (pin "1") (pinfunction "1_1") (pintype "passive"))
      (node (ref "U4") (pin "4") (pinfunction "QE_4") (pintype "tri_state"))
    )
    (net (code "69") (name "Net-(U4A-QF)") (class "Default")
      (node (ref "R67") (pin "1") (pinfunction "1_1") (pintype "passive"))
      (node (ref "U4") (pin "5") (pinfunction "QF_5") (pintype "tri_state"))
    )
    (net (code "70") (name "Net-(U4A-QG)") (class "Default")
      (node (ref "R66") (pin "1") (pinfunction "1_1") (pintype "passive"))
      (node (ref "U4") (pin "6") (pinfunction "QG_6") (pintype "tri_state"))
    )
    (net (code "71") (name "Net-(U4A-QH)") (class "Default")
      (node (ref "R65") (pin "1") (pinfunction "1_1") (pintype "passive"))
      (node (ref "U4") (pin "7") (pinfunction "QH_7") (pintype "tri_state"))
    )
    (net (code "72") (name "RELAY_R1") (class "Default")
      (node (ref "R41") (pin "2") (pinfunction "2_2") (pintype "passive"))
      (node (ref "S1") (pin "P1") (pinfunction "C+_P1") (pintype "bidirectional"))
    )
    (net (code "73") (name "RELAY_R2") (class "Default")
      (node (ref "R42") (pin "2") (pinfunction "2_2") (pintype "passive"))
      (node (ref "S2") (pin "P1") (pinfunction "C+_P1") (pintype "bidirectional"))
    )
    (net (code "74") (name "RELAY_R3") (class "Default")
      (node (ref "R43") (pin "2") (pinfunction "2_2") (pintype "passive"))
      (node (ref "S3") (pin "P1") (pinfunction "C+_P1") (pintype "bidirectional"))
    )
    (net (code "75") (name "RELAY_R4") (class "Default")
      (node (ref "R44") (pin "2") (pinfunction "2_2") (pintype "passive"))
      (node (ref "S4") (pin "P1") (pinfunction "C+_P1") (pintype "bidirectional"))
    )
    (net (code "76") (name "RELAY_R5") (class "Default")
      (node (ref "R45") (pin "2") (pinfunction "2_2") (pintype "passive"))
      (node (ref "S5") (pin "P1") (pinfunction "C+_P1") (pintype "bidirectional"))
    )
    (net (code "77") (name "RELAY_R6") (class "Default")
      (node (ref "R46") (pin "2") (pinfunction "2_2") (pintype "passive"))
      (node (ref "S6") (pin "P1") (pinfunction "C+_P1") (pintype "bidirectional"))
    )
    (net (code "78") (name "RELAY_R7") (class "Default")
      (node (ref "R47") (pin "2") (pinfunction "2_2") (pintype "passive"))
      (node (ref "S7") (pin "P1") (pinfunction "C+_P1") (pintype "bidirectional"))
    )
    (net (code "79") (name "RELAY_R8") (class "Default")
      (node (ref "R48") (pin "2") (pinfunction "2_2") (pintype "passive"))
      (node (ref "S8") (pin "P1") (pinfunction "C+_P1") (pintype "bidirectional"))
    )
    (net (code "80") (name "RELAY_R9") (class "Default")
      (node (ref "R49") (pin "2") (pinfunction "2_2") (pintype "passive"))
      (node (ref "S9") (pin "P1") (pinfunction "C+_P1") (pintype "bidirectional"))
    )
    (net (code "81") (name "RELAY_R10") (class "Default")
      (node (ref "R50") (pin "2") (pinfunction "2_2") (pintype "passive"))
      (node (ref "S10") (pin "P1") (pinfunction "C+_P1") (pintype "bidirectional"))
    )
    (net (code "82") (name "RELAY_R11") (class "Default")
      (node (ref "R51") (pin "2") (pinfunction "2_2") (pintype "passive"))
      (node (ref "S11") (pin "P1") (pinfunction "C+_P1") (pintype "bidirectional"))
    )
    (net (code "83") (name "RELAY_R12") (class "Default")
      (node (ref "R52") (pin "2") (pinfunction "2_2") (pintype "passive"))
      (node (ref "S12") (pin "P1") (pinfunction "C+_P1") (pintype "bidirectional"))
    )
    (net (code "84") (name "RELAY_R13") (class "Default")
      (node (ref "R53") (pin "2") (pinfunction "2_2") (pintype "passive"))
      (node (ref "S13") (pin "P1") (pinfunction "C+_P1") (pintype "bidirectional"))
    )
    (net (code "85") (name "RELAY_R14") (class "Default")
      (node (ref "R54") (pin "2") (pinfunction "2_2") (pintype "passive"))
      (node (ref "S14") (pin "P1") (pinfunction "C+_P1") (pintype "bidirectional"))
    )
    (net (code "86") (name "RELAY_R15") (class "Default")
      (node (ref "R55") (pin "2") (pinfunction "2_2") (pintype "passive"))
      (node (ref "S15") (pin "P1") (pinfunction "C+_P1") (pintype "bidirectional"))
    )
    (net (code "87") (name "RELAY_R16") (class "Default")
      (node (ref "R56") (pin "2") (pinfunction "2_2") (pintype "passive"))
      (node (ref "S16") (pin "P1") (pinfunction "C+_P1") (pintype "bidirectional"))
    )
    (net (code "88") (name "RELAY_R17") (class "Default")
      (node (ref "R57") (pin "2") (pinfunction "2_2") (pintype "passive"))
      (node (ref "S17") (pin "P1") (pinfunction "C+_P1") (pintype "bidirectional"))
    )
    (net (code "89") (name "RELAY_R18") (class "Default")
      (node (ref "R58") (pin "2") (pinfunction "2_2") (pintype "passive"))
      (node (ref "S18") (pin "P1") (pinfunction "C+_P1") (pintype "bidirectional"))
    )
    (net (code "90") (name "RELAY_R19") (class "Default")
      (node (ref "R59") (pin "2") (pinfunction "2_2") (pintype "passive"))
      (node (ref "S19") (pin "P1") (pinfunction "C+_P1") (pintype "bidirectional"))
    )
    (net (code "91") (name "RELAY_R20") (class "Default")
      (node (ref "R60") (pin "2") (pinfunction "2_2") (pintype "passive"))
      (node (ref "S20") (pin "P1") (pinfunction "C+_P1") (pintype "bidirectional"))
    )
    (net (code "92") (name "RELAY_R21") (class "Default")
      (node (ref "R61") (pin "2") (pinfunction "2_2") (pintype "passive"))
      (node (ref "S21") (pin "P1") (pinfunction "C+_P1") (pintype "bidirectional"))
    )
    (net (code "93") (name "RELAY_R22") (class "Default")
      (node (ref "R62") (pin "2") (pinfunction "2_2") (pintype "passive"))
      (node (ref "S22") (pin "P1") (pinfunction "C+_P1") (pintype "bidirectional"))
    )
    (net (code "94") (name "RELAY_R23") (class "Default")
      (node (ref "R63") (pin "2") (pinfunction "2_2") (pintype "passive"))
      (node (ref "S23") (pin "P1") (pinfunction "C+_P1") (pintype "bidirectional"))
    )
    (net (code "95") (name "RELAY_R24") (class "Default")
      (node (ref "R64") (pin "2") (pinfunction "2_2") (pintype "passive"))
      (node (ref "S24") (pin "P1") (pinfunction "C+_P1") (pintype "bidirectional"))
    )
    (net (code "96") (name "RELAY_R25") (class "Default")
      (node (ref "R65") (pin "2") (pinfunction "2_2") (pintype "passive"))
      (node (ref "S25") (pin "P1") (pinfunction "C+_P1") (pintype "bidirectional"))
    )
    (net (code "97") (name "RELAY_R26") (class "Default")
      (node (ref "R66") (pin "2") (pinfunction "2_2") (pintype "passive"))
      (node (ref "S26") (pin "P1") (pinfunction "C+_P1") (pintype "bidirectional"))
    )
    (net (code "98") (name "RELAY_R27") (class "Default")
      (node (ref "R67") (pin "2") (pinfunction "2_2") (pintype "passive"))
      (node (ref "S27") (pin "P1") (pinfunction "C+_P1") (pintype "bidirectional"))
    )
    (net (code "99") (name "RELAY_R28") (class "Default")
      (node (ref "R68") (pin "2") (pinfunction "2_2") (pintype "passive"))
      (node (ref "S28") (pin "P1") (pinfunction "C+_P1") (pintype "bidirectional"))
    )
    (net (code "100") (name "RELAY_R29") (class "Default")
      (node (ref "R69") (pin "2") (pinfunction "2_2") (pintype "passive"))
      (node (ref "S29") (pin "P1") (pinfunction "C+_P1") (pintype "bidirectional"))
    )
    (net (code "101") (name "RELAY_R30") (class "Default")
      (node (ref "R70") (pin "2") (pinfunction "2_2") (pintype "passive"))
      (node (ref "S30") (pin "P1") (pinfunction "C+_P1") (pintype "bidirectional"))
    )
    (net (code "102") (name "RELAY_R31") (class "Default")
      (node (ref "R71") (pin "2") (pinfunction "2_2") (pintype "passive"))
      (node (ref "S31") (pin "P1") (pinfunction "C+_P1") (pintype "bidirectional"))
    )
    (net (code "103") (name "RELAY_R32") (class "Default")
      (node (ref "R72") (pin "2") (pinfunction "2_2") (pintype "passive"))
      (node (ref "S32") (pin "P1") (pinfunction "C+_P1") (pintype "bidirectional"))
    )
    (net (code "104") (name "R_IN") (class "Default")
      (node (ref "JP2") (pin "1") (pinfunction "1_1") (pintype "passive"))
      (node (ref "R1") (pin "2") (pinfunction "2_2") (pintype "passive"))
      (node (ref "S1") (pin "P4") (pinfunction "DC+_P4") (pintype "bidirectional"))
    )
    (net (code "105") (name "R_OUT") (class "Default")
      (node (ref "JP2") (pin "2") (pinfunction "2_2") (pintype "passive"))
      (node (ref "R32") (pin "1") (pinfunction "1_1") (pintype "passive"))
      (node (ref "R320") (pin "1") (pinfunction "1_1") (pintype "passive"))
      (node (ref "S32") (pin "P3") (pinfunction "DC-_P3") (pintype "bidirectional"))
    )
    (net (code "106") (name "SERIAL_CLK") (class "Default")
      (node (ref "JP1") (pin "8") (pinfunction "8_8") (pintype "passive"))
      (node (ref "U1") (pin "11") (pinfunction "SCK_11") (pintype "input"))
      (node (ref "U2") (pin "11") (pinfunction "SCK_11") (pintype "input"))
    )
    (net (code "107") (name "SERIAL_CLK_2") (class "Default")
      (node (ref "JP2") (pin "8") (pinfunction "8_8") (pintype "passive"))
      (node (ref "U3") (pin "11") (pinfunction "SCK_11") (pintype "input"))
      (node (ref "U4") (pin "11") (pinfunction "SCK_11") (pintype "input"))
    )
    (net (code "108") (name "SERIAL_IN") (class "Default")
      (node (ref "JP2") (pin "4") (pinfunction "4_4") (pintype "passive"))
      (node (ref "U1") (pin "14") (pinfunction "SER_14") (pintype "input"))
    )
    (net (code "109") (name "SERIAL_LATCH") (class "Default")
      (node (ref "JP1") (pin "9") (pinfunction "9_9") (pintype "passive"))
      (node (ref "U1") (pin "12") (pinfunction "RCK_12") (pintype "input"))
      (node (ref "U2") (pin "12") (pinfunction "RCK_12") (pintype "input"))
    )
    (net (code "110") (name "SERIAL_LATCH_2") (class "Default")
      (node (ref "JP2") (pin "9") (pinfunction "9_9") (pintype "passive"))
      (node (ref "U3") (pin "12") (pinfunction "RCK_12") (pintype "input"))
      (node (ref "U4") (pin "12") (pinfunction "RCK_12") (pintype "input"))
    )
    (net (code "111") (name "SERIAL_MR_L") (class "Default")
      (node (ref "JP1") (pin "7") (pinfunction "7_7") (pintype "passive"))
      (node (ref "U1") (pin "10") (pinfunction "SCL_10") (pintype "input"))
      (node (ref "U2") (pin "10") (pinfunction "SCL_10") (pintype "input"))
    )
    (net (code "112") (name "SERIAL_MR_L_2") (class "Default")
      (node (ref "JP2") (pin "7") (pinfunction "7_7") (pintype "passive"))
      (node (ref "U3") (pin "10") (pinfunction "SCL_10") (pintype "input"))
      (node (ref "U4") (pin "10") (pinfunction "SCL_10") (pintype "input"))
    )
    (net (code "113") (name "SERIAL_OE_L") (class "Default")
      (node (ref "JP1") (pin "10") (pinfunction "10_10") (pintype "passive"))
      (node (ref "U1") (pin "13") (pinfunction "G_13") (pintype "input"))
      (node (ref "U2") (pin "13") (pinfunction "G_13") (pintype "input"))
    )
    (net (code "114") (name "SERIAL_OE_L_2") (class "Default")
      (node (ref "JP2") (pin "10") (pinfunction "10_10") (pintype "passive"))
      (node (ref "U3") (pin "13") (pinfunction "G_13") (pintype "input"))
      (node (ref "U4") (pin "13") (pinfunction "G_13") (pintype "input"))
    )
    (net (code "115") (name "SERIAL_PASS") (class "Default")
      (node (ref "U1") (pin "9") (pinfunction "QH*_9") (pintype "tri_state"))
      (node (ref "U2") (pin "14") (pinfunction "SER_14") (pintype "input"))
    )
    (net (code "116") (name "SERIAL_PASS1") (class "Default")
      (node (ref "U2") (pin "9") (pinfunction "QH*_9") (pintype "tri_state"))
      (node (ref "U3") (pin "14") (pinfunction "SER_14") (pintype "input"))
    )
    (net (code "117") (name "SERIAL_PASS2") (class "Default")
      (node (ref "U3") (pin "9") (pinfunction "QH*_9") (pintype "tri_state"))
      (node (ref "U4") (pin "14") (pinfunction "SER_14") (pintype "input"))
    )
    (net (code "118") (name "unconnected-(JP2-Pad3)") (class "Default")
      (node (ref "JP2") (pin "3") (pinfunction "3_3") (pintype "passive"))
    )
    (net (code "119") (name "unconnected-(U4A-QH*-Pad9)") (class "Default")
      (node (ref "U4") (pin "9") (pinfunction "QH*_9") (pintype "tri_state"))
    )
  )
)
